# Output_Circuit.net
KiCad netlist of a schematic drawn in Altium Designer
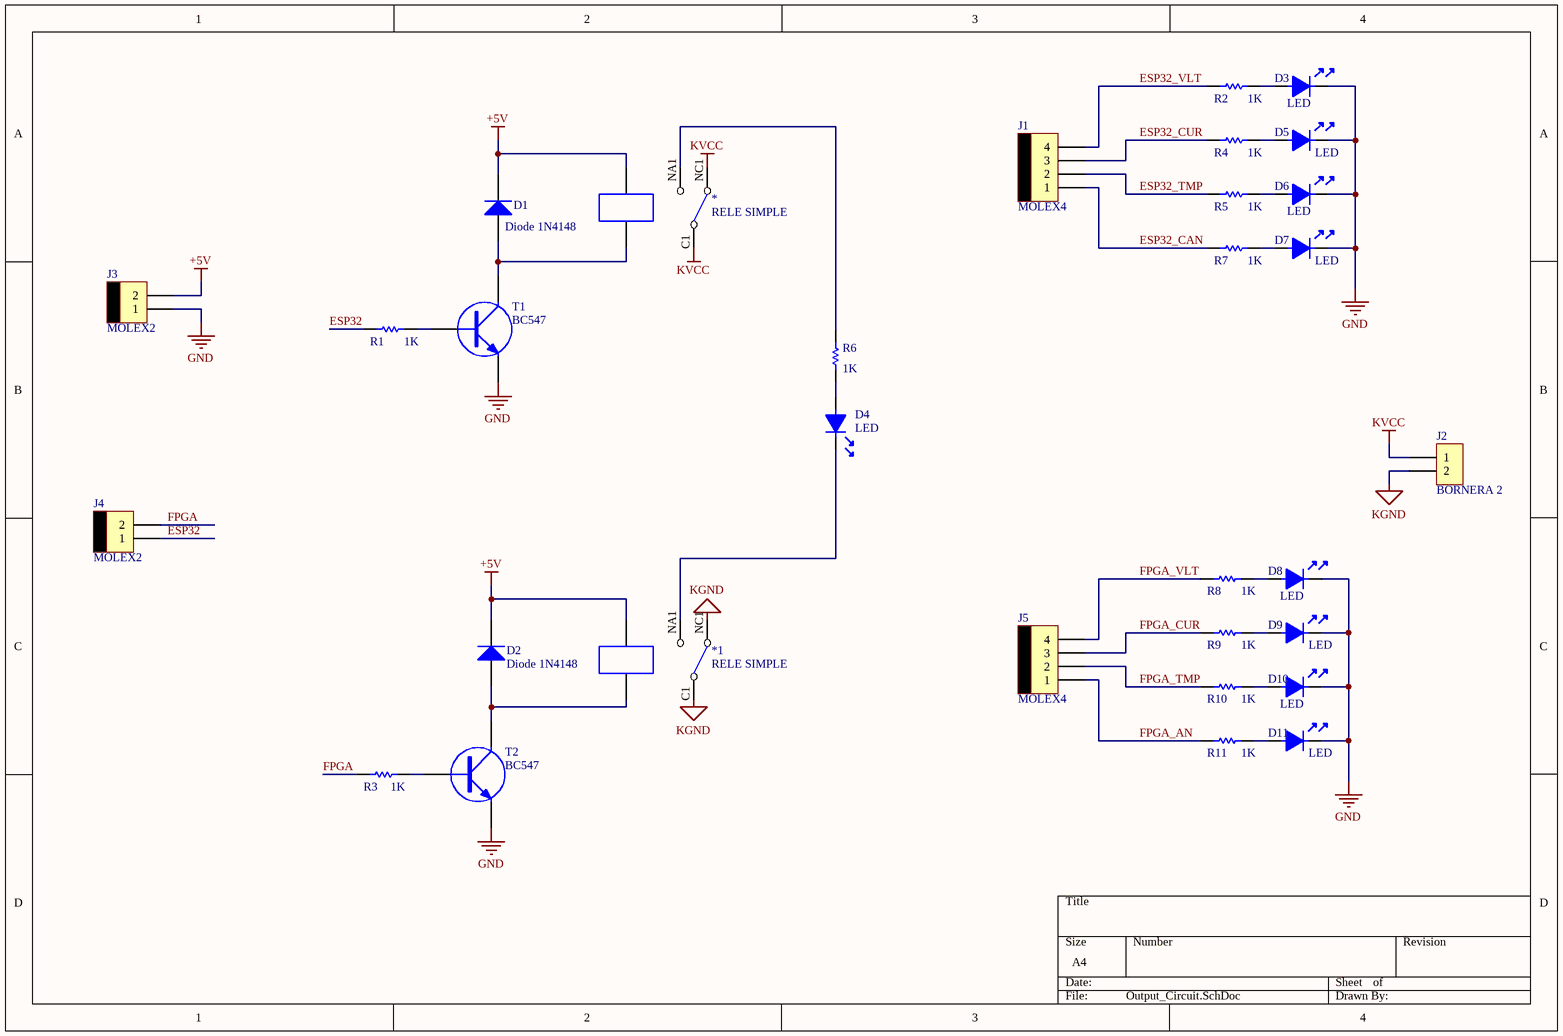
[diagram p0: Output_Circuit.SchDoc]

(export (version "E")
  (design (tool "Eeschema 10.0.6"))
  (components
    (comp (ref "*")
      (value "RELE SIMPLE")
      (footprint "RELE SERIE 964")
      (libsource (lib "LIBEBAL") (part "RELE SIMPLE"))
    )
    (comp (ref "*1")
      (value "RELE SIMPLE")
      (footprint "RELE SERIE 964")
      (libsource (lib "LIBEBAL") (part "RELE SIMPLE"))
    )
    (comp (ref "D1")
      (value "Diode 1N4148")
      (footprint "DO-35")
      (description "High Conductance Fast Diode")
      (fields (field (name "PUBLISHER") "Altium Limited"))
      (libsource (lib "TD") (part "Diode 1N5408"))
    )
    (comp (ref "D2")
      (value "Diode 1N4148")
      (footprint "DO-35")
      (description "High Conductance Fast Diode")
      (fields (field (name "PUBLISHER") "Altium Limited"))
      (libsource (lib "TD") (part "Diode 1N5408"))
    )
    (comp (ref "D3") (value "LED") (footprint "LED5") (libsource (lib "TD") (part "LED")))
    (comp (ref "D4") (value "LED") (footprint "LED5") (libsource (lib "TD") (part "LED")))
    (comp (ref "D5") (value "LED") (footprint "LED5") (libsource (lib "TD") (part "LED")))
    (comp (ref "D6") (value "LED") (footprint "LED5") (libsource (lib "TD") (part "LED")))
    (comp (ref "D7") (value "LED") (footprint "LED5") (libsource (lib "TD") (part "LED")))
    (comp (ref "D8") (value "LED") (footprint "LED5") (libsource (lib "TD") (part "LED")))
    (comp (ref "D9") (value "LED") (footprint "LED5") (libsource (lib "TD") (part "LED")))
    (comp (ref "D10") (value "LED") (footprint "LED5") (libsource (lib "TD") (part "LED")))
    (comp (ref "D11") (value "LED") (footprint "LED5") (libsource (lib "TD") (part "LED")))
    (comp (ref "J1") (value "MOLEX4") (footprint "MOLEX4") (libsource (lib "LIBEBAL") (part "MOLEX4")))
    (comp (ref "J2") (value "BORNERA 2") (footprint "BORNERA2") (libsource (lib "TD") (part "BORNERA 2")))
    (comp (ref "J3") (value "MOLEX2") (footprint "MOLEX2") (libsource (lib "LIBEBAL") (part "MOLEX2")))
    (comp (ref "J4") (value "MOLEX2") (footprint "MOLEX2") (libsource (lib "LIBEBAL") (part "MOLEX2")))
    (comp (ref "J5") (value "MOLEX4") (footprint "MOLEX4") (libsource (lib "LIBEBAL") (part "MOLEX4")))
    (comp (ref "R1") (value "1K") (footprint "RES400") (libsource (lib "TD") (part "RES")))
    (comp (ref "R2") (value "1K") (footprint "RES400") (libsource (lib "TD") (part "RES")))
    (comp (ref "R3") (value "1K") (footprint "RES400") (libsource (lib "TD") (part "RES")))
    (comp (ref "R4") (value "1K") (footprint "RES400") (libsource (lib "TD") (part "RES")))
    (comp (ref "R5") (value "1K") (footprint "RES400") (libsource (lib "TD") (part "RES")))
    (comp (ref "R6") (value "1K") (footprint "RES400") (libsource (lib "TD") (part "RES")))
    (comp (ref "R7") (value "1K") (footprint "RES400") (libsource (lib "TD") (part "RES")))
    (comp (ref "R8") (value "1K") (footprint "RES400") (libsource (lib "TD") (part "RES")))
    (comp (ref "R9") (value "1K") (footprint "RES400") (libsource (lib "TD") (part "RES")))
    (comp (ref "R10") (value "1K") (footprint "RES400") (libsource (lib "TD") (part "RES")))
    (comp (ref "R11") (value "1K") (footprint "RES400") (libsource (lib "TD") (part "RES")))
    (comp (ref "T1") (value "BC547") (footprint "TO92") (libsource (lib "TD") (part "TRANSISTOR NPN")))
    (comp (ref "T2") (value "BC547") (footprint "TO92") (libsource (lib "TD") (part "TRANSISTOR NPN")))
  )
  (nets
    (net (code "1") (name "+5V") (class "Default")
      (node (ref "*") (pin "B1") (pinfunction "B1_B1") (pintype "passive"))
      (node (ref "*1") (pin "B1") (pinfunction "B1_B1") (pintype "passive"))
      (node (ref "D1") (pin "2") (pinfunction "K_2") (pintype "passive"))
      (node (ref "D2") (pin "2") (pinfunction "K_2") (pintype "passive"))
      (node (ref "J3") (pin "2") (pinfunction "2_2") (pintype "passive"))
    )
    (net (code "2") (name "/ESP32") (class "Default")
      (node (ref "J4") (pin "1") (pinfunction "1_1") (pintype "passive"))
      (node (ref "R1") (pin "1") (pinfunction "1_1") (pintype "passive"))
    )
    (net (code "3") (name "/ESP32_CAN") (class "Default")
      (node (ref "J1") (pin "1") (pinfunction "1_1") (pintype "passive"))
      (node (ref "R7") (pin "1") (pinfunction "1_1") (pintype "passive"))
    )
    (net (code "4") (name "/ESP32_CUR") (class "Default")
      (node (ref "J1") (pin "3") (pinfunction "3_3") (pintype "passive"))
      (node (ref "R4") (pin "1") (pinfunction "1_1") (pintype "passive"))
    )
    (net (code "5") (name "/ESP32_TMP") (class "Default")
      (node (ref "J1") (pin "2") (pinfunction "2_2") (pintype "passive"))
      (node (ref "R5") (pin "1") (pinfunction "1_1") (pintype "passive"))
    )
    (net (code "6") (name "/ESP32_VLT") (class "Default")
      (node (ref "J1") (pin "4") (pinfunction "4_4") (pintype "passive"))
      (node (ref "R2") (pin "1") (pinfunction "1_1") (pintype "passive"))
    )
    (net (code "7") (name "/FPGA") (class "Default")
      (node (ref "J4") (pin "2") (pinfunction "2_2") (pintype "passive"))
      (node (ref "R3") (pin "1") (pinfunction "1_1") (pintype "passive"))
    )
    (net (code "8") (name "/FPGA_AN") (class "Default")
      (node (ref "J5") (pin "1") (pinfunction "1_1") (pintype "passive"))
      (node (ref "R11") (pin "1") (pinfunction "1_1") (pintype "passive"))
    )
    (net (code "9") (name "/FPGA_CUR") (class "Default")
      (node (ref "J5") (pin "3") (pinfunction "3_3") (pintype "passive"))
      (node (ref "R9") (pin "1") (pinfunction "1_1") (pintype "passive"))
    )
    (net (code "10") (name "/FPGA_TMP") (class "Default")
      (node (ref "J5") (pin "2") (pinfunction "2_2") (pintype "passive"))
      (node (ref "R10") (pin "1") (pinfunction "1_1") (pintype "passive"))
    )
    (net (code "11") (name "/FPGA_VLT") (class "Default")
      (node (ref "J5") (pin "4") (pinfunction "4_4") (pintype "passive"))
      (node (ref "R8") (pin "1") (pinfunction "1_1") (pintype "passive"))
    )
    (net (code "12") (name "GND") (class "Default")
      (node (ref "D10") (pin "2") (pinfunction "2_2") (pintype "passive"))
      (node (ref "D11") (pin "2") (pinfunction "2_2") (pintype "passive"))
      (node (ref "D3") (pin "2") (pinfunction "2_2") (pintype "passive"))
      (node (ref "D5") (pin "2") (pinfunction "2_2") (pintype "passive"))
      (node (ref "D6") (pin "2") (pinfunction "2_2") (pintype "passive"))
      (node (ref "D7") (pin "2") (pinfunction "2_2") (pintype "passive"))
      (node (ref "D8") (pin "2") (pinfunction "2_2") (pintype "passive"))
      (node (ref "D9") (pin "2") (pinfunction "2_2") (pintype "passive"))
      (node (ref "J3") (pin "1") (pinfunction "1_1") (pintype "passive"))
      (node (ref "T1") (pin "3") (pinfunction "E_3") (pintype "passive"))
      (node (ref "T2") (pin "3") (pinfunction "E_3") (pintype "passive"))
    )
    (net (code "13") (name "KGND") (class "Default")
      (node (ref "*1") (pin "C1") (pinfunction "C1_C1") (pintype "passive"))
      (node (ref "*1") (pin "NC1") (pinfunction "NC1_NC1") (pintype "passive"))
      (node (ref "J2") (pin "2") (pinfunction "2_2") (pintype "passive"))
    )
    (net (code "14") (name "KVCC") (class "Default")
      (node (ref "*") (pin "C1") (pinfunction "C1_C1") (pintype "passive"))
      (node (ref "*") (pin "NC1") (pinfunction "NC1_NC1") (pintype "passive"))
      (node (ref "J2") (pin "1") (pinfunction "1_1") (pintype "passive"))
    )
    (net (code "15") (name "Net-(*-PadNA1)") (class "Default")
      (node (ref "*") (pin "NA1") (pinfunction "NA1_NA1") (pintype "passive"))
      (node (ref "R6") (pin "2") (pinfunction "2_2") (pintype "passive"))
    )
    (net (code "16") (name "Net-(*1-PadNA1)") (class "Default")
      (node (ref "*1") (pin "NA1") (pinfunction "NA1_NA1") (pintype "passive"))
      (node (ref "D4") (pin "2") (pinfunction "2_2") (pintype "passive"))
    )
    (net (code "17") (name "Net-(D1-A)") (class "Default")
      (node (ref "*") (pin "B2") (pinfunction "B2_B2") (pintype "passive"))
      (node (ref "D1") (pin "1") (pinfunction "A_1") (pintype "passive"))
      (node (ref "T1") (pin "2") (pinfunction "C_2") (pintype "passive"))
    )
    (net (code "18") (name "Net-(D2-A)") (class "Default")
      (node (ref "*1") (pin "B2") (pinfunction "B2_B2") (pintype "passive"))
      (node (ref "D2") (pin "1") (pinfunction "A_1") (pintype "passive"))
      (node (ref "T2") (pin "2") (pinfunction "C_2") (pintype "passive"))
    )
    (net (code "19") (name "Net-(D3-Pad1)") (class "Default")
      (node (ref "D3") (pin "1") (pinfunction "1_1") (pintype "passive"))
      (node (ref "R2") (pin "2") (pinfunction "2_2") (pintype "passive"))
    )
    (net (code "20") (name "Net-(D4-Pad1)") (class "Default")
      (node (ref "D4") (pin "1") (pinfunction "1_1") (pintype "passive"))
      (node (ref "R6") (pin "1") (pinfunction "1_1") (pintype "passive"))
    )
    (net (code "21") (name "Net-(D5-Pad1)") (class "Default")
      (node (ref "D5") (pin "1") (pinfunction "1_1") (pintype "passive"))
      (node (ref "R4") (pin "2") (pinfunction "2_2") (pintype "passive"))
    )
    (net (code "22") (name "Net-(D6-Pad1)") (class "Default")
      (node (ref "D6") (pin "1") (pinfunction "1_1") (pintype "passive"))
      (node (ref "R5") (pin "2") (pinfunction "2_2") (pintype "passive"))
    )
    (net (code "23") (name "Net-(D7-Pad1)") (class "Default")
      (node (ref "D7") (pin "1") (pinfunction "1_1") (pintype "passive"))
      (node (ref "R7") (pin "2") (pinfunction "2_2") (pintype "passive"))
    )
    (net (code "24") (name "Net-(D8-Pad1)") (class "Default")
      (node (ref "D8") (pin "1") (pinfunction "1_1") (pintype "passive"))
      (node (ref "R8") (pin "2") (pinfunction "2_2") (pintype "passive"))
    )
    (net (code "25") (name "Net-(D9-Pad1)") (class "Default")
      (node (ref "D9") (pin "1") (pinfunction "1_1") (pintype "passive"))
      (node (ref "R9") (pin "2") (pinfunction "2_2") (pintype "passive"))
    )
    (net (code "26") (name "Net-(D10-Pad1)") (class "Default")
      (node (ref "D10") (pin "1") (pinfunction "1_1") (pintype "passive"))
      (node (ref "R10") (pin "2") (pinfunction "2_2") (pintype "passive"))
    )
    (net (code "27") (name "Net-(D11-Pad1)") (class "Default")
      (node (ref "D11") (pin "1") (pinfunction "1_1") (pintype "passive"))
      (node (ref "R11") (pin "2") (pinfunction "2_2") (pintype "passive"))
    )
    (net (code "28") (name "Net-(T1-B)") (class "Default")
      (node (ref "R1") (pin "2") (pinfunction "2_2") (pintype "passive"))
      (node (ref "T1") (pin "1") (pinfunction "B_1") (pintype "passive"))
    )
    (net (code "29") (name "Net-(T2-B)") (class "Default")
      (node (ref "R3") (pin "2") (pinfunction "2_2") (pintype "passive"))
      (node (ref "T2") (pin "1") (pinfunction "B_1") (pintype "passive"))
    )
  )
)
